# 2020can_master_v6.net
KiCad netlist of a schematic drawn in EAGLE
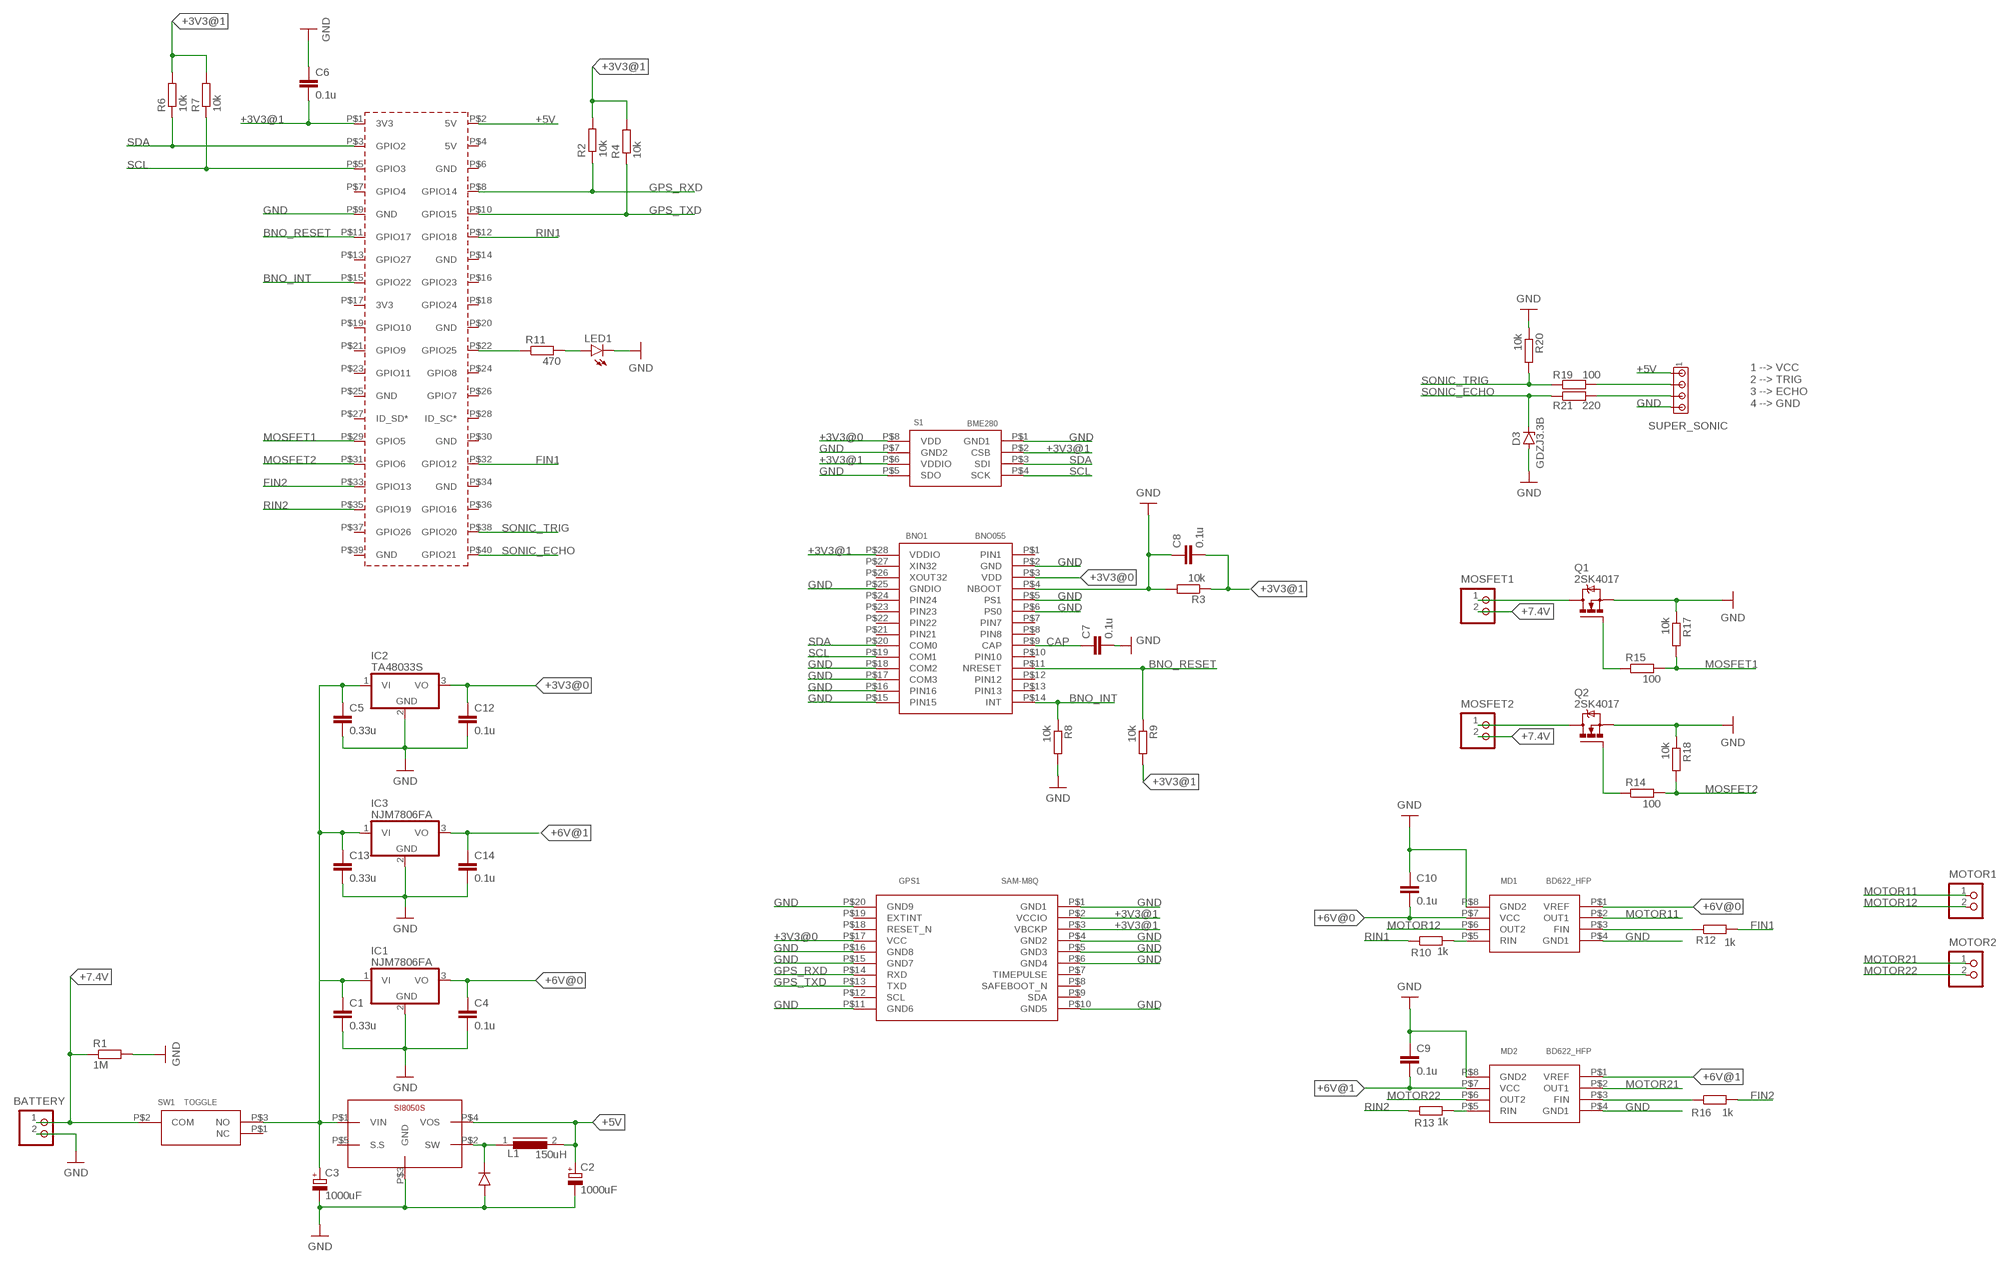
[diagram p0: schematic, sheet 1]

(export (version "E")
  (design (tool "Eeschema 10.0.6"))
  (components
    (comp (ref "BATTERY")
      (value "B2P-VH")
      (footprint "eagle-import:B2P-VH")
      (libsource (lib "eagle-import") (part "B2P-VH"))
    )
    (comp (ref "BNO1")
      (value "BNO055")
      (footprint "eagle-import:BNO055")
      (libsource (lib "eagle-import") (part "BNO055"))
    )
    (comp (ref "C1")
      (value "0.33u")
      (footprint "eagle-import:C5B3")
      (libsource (lib "eagle-import") (part "C5/3"))
    )
    (comp (ref "C2")
      (value "1000uF")
      (footprint "eagle-import:E5-10,5")
      (libsource (lib "eagle-import") (part "CPOL-EUE5-10.5"))
    )
    (comp (ref "C3")
      (value "1000uF")
      (footprint "eagle-import:E5-10,5")
      (libsource (lib "eagle-import") (part "CPOL-EUE5-10.5"))
    )
    (comp (ref "C4")
      (value "0.1u")
      (footprint "eagle-import:C5B3")
      (libsource (lib "eagle-import") (part "C5/3"))
    )
    (comp (ref "C5")
      (value "0.33u")
      (footprint "eagle-import:C5B3")
      (libsource (lib "eagle-import") (part "C5/3"))
    )
    (comp (ref "C6")
      (value "0.1u")
      (footprint "eagle-import:C1608")
      (libsource (lib "eagle-import") (part "C-EUC1608"))
    )
    (comp (ref "C7")
      (value "0.1u")
      (footprint "eagle-import:C1608")
      (libsource (lib "eagle-import") (part "C-EUC1608"))
    )
    (comp (ref "C8")
      (value "0.1u")
      (footprint "eagle-import:C1608")
      (libsource (lib "eagle-import") (part "C-EUC1608"))
    )
    (comp (ref "C9")
      (value "0.1u")
      (footprint "eagle-import:C1608")
      (libsource (lib "eagle-import") (part "C-EUC1608"))
    )
    (comp (ref "C10")
      (value "0.1u")
      (footprint "eagle-import:C1608")
      (libsource (lib "eagle-import") (part "C-EUC1608"))
    )
    (comp (ref "C12")
      (value "0.1u")
      (footprint "eagle-import:C5B3")
      (libsource (lib "eagle-import") (part "C5/3"))
    )
    (comp (ref "C13")
      (value "0.33u")
      (footprint "eagle-import:C5B3")
      (libsource (lib "eagle-import") (part "C5/3"))
    )
    (comp (ref "C14")
      (value "0.1u")
      (footprint "eagle-import:C5B3")
      (libsource (lib "eagle-import") (part "C5/3"))
    )
    (comp (ref "D3")
      (value "GDZJ3.3B")
      (footprint "eagle-import:DO35Z10")
      (libsource (lib "eagle-import") (part "1N821"))
    )
    (comp (ref "DIODE_1.1")
      (value "DIODE_1.5")
      (footprint "eagle-import:DIODE_1.5")
      (libsource (lib "eagle-import") (part "DIODE_1.5"))
    )
    (comp (ref "GPS1")
      (value "SAM-M8Q")
      (footprint "eagle-import:SAM-M8Q")
      (libsource (lib "eagle-import") (part "SAM-M8Q"))
    )
    (comp (ref "IC1")
      (value "NJM7806FA")
      (footprint "eagle-import:TO220V")
      (libsource (lib "eagle-import") (part "78TV6"))
    )
    (comp (ref "IC2")
      (value "TA48033S")
      (footprint "eagle-import:TO220V")
      (libsource (lib "eagle-import") (part "78TV6"))
    )
    (comp (ref "IC3")
      (value "NJM7806FA")
      (footprint "eagle-import:TO220V")
      (libsource (lib "eagle-import") (part "78TV6"))
    )
    (comp (ref "L1")
      (value "150uH")
      (footprint "eagle-import:SFT830D")
      (libsource (lib "eagle-import") (part "SFT830D"))
    )
    (comp (ref "LED1")
      (value "LED5MM")
      (footprint "eagle-import:LED5MM")
      (libsource (lib "eagle-import") (part "LED5MM"))
    )
    (comp (ref "MD1")
      (value "BD622_HFP")
      (footprint "eagle-import:BD62___HRP7")
      (libsource (lib "eagle-import") (part "BD622_HFP"))
    )
    (comp (ref "MD2")
      (value "BD622_HFP")
      (footprint "eagle-import:BD62___HRP7")
      (libsource (lib "eagle-import") (part "BD622_HFP"))
    )
    (comp (ref "MOSFET1")
      (value "B2P-VH")
      (footprint "eagle-import:B2P-VH")
      (libsource (lib "eagle-import") (part "B2P-VH"))
    )
    (comp (ref "MOSFET2")
      (value "B2P-VH")
      (footprint "eagle-import:B2P-VH")
      (libsource (lib "eagle-import") (part "B2P-VH"))
    )
    (comp (ref "MOTOR1")
      (value "B2P-VH")
      (footprint "eagle-import:B2P-VH")
      (libsource (lib "eagle-import") (part "B2P-VH"))
    )
    (comp (ref "MOTOR2")
      (value "B2P-VH")
      (footprint "eagle-import:B2P-VH")
      (libsource (lib "eagle-import") (part "B2P-VH"))
    )
    (comp (ref "PCB1")
      (value "RPI3RPI3")
      (footprint "eagle-import:RPI3")
      (libsource (lib "eagle-import") (part "RPI3RPI3"))
    )
    (comp (ref "Q1")
      (value "2SK4017")
      (footprint "eagle-import:TO220BV")
      (libsource (lib "eagle-import") (part "IRF520"))
    )
    (comp (ref "Q2")
      (value "2SK4017")
      (footprint "eagle-import:TO220BV")
      (libsource (lib "eagle-import") (part "IRF520"))
    )
    (comp (ref "R1")
      (value "1M")
      (footprint "eagle-import:R2012")
      (libsource (lib "eagle-import") (part "R-EU_R2012"))
    )
    (comp (ref "R2")
      (value "10k")
      (footprint "eagle-import:R2012")
      (libsource (lib "eagle-import") (part "R-EU_R2012"))
    )
    (comp (ref "R3")
      (value "10k")
      (footprint "eagle-import:R2012")
      (libsource (lib "eagle-import") (part "R-EU_R2012"))
    )
    (comp (ref "R4")
      (value "10k")
      (footprint "eagle-import:R2012")
      (libsource (lib "eagle-import") (part "R-EU_R2012"))
    )
    (comp (ref "R6")
      (value "10k")
      (footprint "eagle-import:R2012")
      (libsource (lib "eagle-import") (part "R-EU_R2012"))
    )
    (comp (ref "R7")
      (value "10k")
      (footprint "eagle-import:R2012")
      (libsource (lib "eagle-import") (part "R-EU_R2012"))
    )
    (comp (ref "R8")
      (value "10k")
      (footprint "eagle-import:R2012")
      (libsource (lib "eagle-import") (part "R-EU_R2012"))
    )
    (comp (ref "R9")
      (value "10k")
      (footprint "eagle-import:R2012")
      (libsource (lib "eagle-import") (part "R-EU_R2012"))
    )
    (comp (ref "R10")
      (value "1k")
      (footprint "eagle-import:R2012")
      (libsource (lib "eagle-import") (part "R-EU_R2012"))
    )
    (comp (ref "R11")
      (value "470")
      (footprint "eagle-import:0207_10")
      (libsource (lib "eagle-import") (part "R-EU_0207/10"))
    )
    (comp (ref "R12")
      (value "1k")
      (footprint "eagle-import:R2012")
      (libsource (lib "eagle-import") (part "R-EU_R2012"))
    )
    (comp (ref "R13")
      (value "1k")
      (footprint "eagle-import:R2012")
      (libsource (lib "eagle-import") (part "R-EU_R2012"))
    )
    (comp (ref "R14")
      (value "100")
      (footprint "eagle-import:0207_10")
      (libsource (lib "eagle-import") (part "R-EU_0207/10"))
    )
    (comp (ref "R15")
      (value "100")
      (footprint "eagle-import:0207_10")
      (libsource (lib "eagle-import") (part "R-EU_0207/10"))
    )
    (comp (ref "R16")
      (value "1k")
      (footprint "eagle-import:R2012")
      (libsource (lib "eagle-import") (part "R-EU_R2012"))
    )
    (comp (ref "R17")
      (value "10k")
      (footprint "eagle-import:R2012")
      (libsource (lib "eagle-import") (part "R-EU_R2012"))
    )
    (comp (ref "R18")
      (value "10k")
      (footprint "eagle-import:R2012")
      (libsource (lib "eagle-import") (part "R-EU_R2012"))
    )
    (comp (ref "R19")
      (value "100")
      (footprint "eagle-import:0207_10")
      (libsource (lib "eagle-import") (part "R-EU_0207/10"))
    )
    (comp (ref "R20")
      (value "10k")
      (footprint "eagle-import:R2012")
      (libsource (lib "eagle-import") (part "R-EU_R2012"))
    )
    (comp (ref "R21")
      (value "220")
      (footprint "eagle-import:0207_10")
      (libsource (lib "eagle-import") (part "R-EU_0207/10"))
    )
    (comp (ref "S1")
      (value "BME280")
      (footprint "eagle-import:BME280")
      (libsource (lib "eagle-import") (part "BME280"))
    )
    (comp (ref "SI8050S1")
      (value "SI8050S")
      (footprint "eagle-import:SI8050S")
      (libsource (lib "eagle-import") (part "SI8050S"))
    )
    (comp (ref "SUPER_SONIC")
      (value "MTA04-100")
      (footprint "eagle-import:10X04MTA")
      (libsource (lib "eagle-import") (part "MTA04-100"))
    )
    (comp (ref "SW1")
      (value "TOGGLE")
      (footprint "eagle-import:TOGGLE_1MS1-T1-B1-M2-Q-N-S")
      (libsource (lib "eagle-import") (part "TOGGLE_1MS1-T1-B1-M2-Q-N-S"))
    )
  )
  (nets
    (net (code "1") (name "+3V3@0") (class "Default")
      (node (ref "BNO1") (pin "P$3") (pinfunction "VDD_P$3") (pintype "bidirectional"))
      (node (ref "C12") (pin "1") (pinfunction "1_1") (pintype "passive"))
      (node (ref "GPS1") (pin "P$17") (pinfunction "VCC_P$17") (pintype "bidirectional"))
      (node (ref "IC2") (pin "3") (pinfunction "VO_3") (pintype "passive"))
      (node (ref "S1") (pin "P$8") (pinfunction "VDD_P$8") (pintype "bidirectional"))
    )
    (net (code "2") (name "+3V3@1") (class "Default")
      (node (ref "BNO1") (pin "P$28") (pinfunction "VDDIO_P$28") (pintype "bidirectional"))
      (node (ref "C6") (pin "2") (pinfunction "2_2") (pintype "passive"))
      (node (ref "C8") (pin "2") (pinfunction "2_2") (pintype "passive"))
      (node (ref "GPS1") (pin "P$2") (pinfunction "VCCIO_P$2") (pintype "bidirectional"))
      (node (ref "GPS1") (pin "P$3") (pinfunction "VBCKP_P$3") (pintype "bidirectional"))
      (node (ref "PCB1") (pin "P$1") (pinfunction "3V3_P$1") (pintype "bidirectional"))
      (node (ref "R2") (pin "2") (pinfunction "2_2") (pintype "passive"))
      (node (ref "R3") (pin "1") (pinfunction "1_1") (pintype "passive"))
      (node (ref "R4") (pin "2") (pinfunction "2_2") (pintype "passive"))
      (node (ref "R6") (pin "2") (pinfunction "2_2") (pintype "passive"))
      (node (ref "R7") (pin "2") (pinfunction "2_2") (pintype "passive"))
      (node (ref "R9") (pin "2") (pinfunction "2_2") (pintype "passive"))
      (node (ref "S1") (pin "P$2") (pinfunction "CSB_P$2") (pintype "bidirectional"))
      (node (ref "S1") (pin "P$6") (pinfunction "VDDIO_P$6") (pintype "bidirectional"))
    )
    (net (code "3") (name "+5V") (class "Default")
      (node (ref "C2") (pin "+") (pinfunction "+_+") (pintype "passive"))
      (node (ref "L1") (pin "2") (pinfunction "2_2") (pintype "passive"))
      (node (ref "PCB1") (pin "P$2") (pinfunction "5V_P$2") (pintype "bidirectional"))
      (node (ref "SI8050S1") (pin "P$4") (pinfunction "VOS_P$4") (pintype "bidirectional"))
      (node (ref "SUPER_SONIC") (pin "1") (pinfunction "1_1") (pintype "passive"))
    )
    (net (code "4") (name "+6V@0") (class "Default")
      (node (ref "C10") (pin "2") (pinfunction "2_2") (pintype "passive"))
      (node (ref "C4") (pin "1") (pinfunction "1_1") (pintype "passive"))
      (node (ref "IC1") (pin "3") (pinfunction "VO_3") (pintype "passive"))
      (node (ref "MD1") (pin "P$1") (pinfunction "VREF_P$1") (pintype "bidirectional"))
      (node (ref "MD1") (pin "P$7") (pinfunction "VCC_P$7") (pintype "bidirectional"))
    )
    (net (code "5") (name "+6V@1") (class "Default")
      (node (ref "C14") (pin "1") (pinfunction "1_1") (pintype "passive"))
      (node (ref "C9") (pin "2") (pinfunction "2_2") (pintype "passive"))
      (node (ref "IC3") (pin "3") (pinfunction "VO_3") (pintype "passive"))
      (node (ref "MD2") (pin "P$1") (pinfunction "VREF_P$1") (pintype "bidirectional"))
      (node (ref "MD2") (pin "P$7") (pinfunction "VCC_P$7") (pintype "bidirectional"))
    )
    (net (code "6") (name "+7.4V") (class "Default")
      (node (ref "BATTERY") (pin "1") (pinfunction "1_1") (pintype "passive"))
      (node (ref "MOSFET1") (pin "2") (pinfunction "2_2") (pintype "passive"))
      (node (ref "MOSFET2") (pin "2") (pinfunction "2_2") (pintype "passive"))
      (node (ref "R1") (pin "1") (pinfunction "1_1") (pintype "passive"))
      (node (ref "SW1") (pin "P$2") (pinfunction "COM_P$2") (pintype "bidirectional"))
    )
    (net (code "7") (name "/BNO_INT") (class "Default")
      (node (ref "BNO1") (pin "P$14") (pinfunction "INT_P$14") (pintype "bidirectional"))
      (node (ref "PCB1") (pin "P$15") (pinfunction "GPIO22_P$15") (pintype "bidirectional"))
      (node (ref "R8") (pin "1") (pinfunction "1_1") (pintype "passive"))
    )
    (net (code "8") (name "/BNO_RESET") (class "Default")
      (node (ref "BNO1") (pin "P$11") (pinfunction "NRESET_P$11") (pintype "bidirectional"))
      (node (ref "PCB1") (pin "P$11") (pinfunction "GPIO17_P$11") (pintype "bidirectional"))
      (node (ref "R9") (pin "1") (pinfunction "1_1") (pintype "passive"))
    )
    (net (code "9") (name "/CAP") (class "Default")
      (node (ref "BNO1") (pin "P$9") (pinfunction "CAP_P$9") (pintype "bidirectional"))
      (node (ref "C7") (pin "1") (pinfunction "1_1") (pintype "passive"))
    )
    (net (code "10") (name "/FIN1") (class "Default")
      (node (ref "PCB1") (pin "P$32") (pinfunction "GPIO12_P$32") (pintype "bidirectional"))
      (node (ref "R12") (pin "2") (pinfunction "2_2") (pintype "passive"))
    )
    (net (code "11") (name "/FIN2") (class "Default")
      (node (ref "PCB1") (pin "P$33") (pinfunction "GPIO13_P$33") (pintype "bidirectional"))
      (node (ref "R16") (pin "2") (pinfunction "2_2") (pintype "passive"))
    )
    (net (code "12") (name "/GPS_RXD") (class "Default")
      (node (ref "GPS1") (pin "P$14") (pinfunction "RXD_P$14") (pintype "bidirectional"))
      (node (ref "PCB1") (pin "P$8") (pinfunction "GPIO14_P$8") (pintype "bidirectional"))
      (node (ref "R2") (pin "1") (pinfunction "1_1") (pintype "passive"))
    )
    (net (code "13") (name "/GPS_TXD") (class "Default")
      (node (ref "GPS1") (pin "P$13") (pinfunction "TXD_P$13") (pintype "bidirectional"))
      (node (ref "PCB1") (pin "P$10") (pinfunction "GPIO15_P$10") (pintype "bidirectional"))
      (node (ref "R4") (pin "1") (pinfunction "1_1") (pintype "passive"))
    )
    (net (code "14") (name "/MOSFET1") (class "Default")
      (node (ref "PCB1") (pin "P$29") (pinfunction "GPIO5_P$29") (pintype "bidirectional"))
      (node (ref "R15") (pin "2") (pinfunction "2_2") (pintype "passive"))
      (node (ref "R17") (pin "2") (pinfunction "2_2") (pintype "passive"))
    )
    (net (code "15") (name "/MOSFET2") (class "Default")
      (node (ref "PCB1") (pin "P$31") (pinfunction "GPIO6_P$31") (pintype "bidirectional"))
      (node (ref "R14") (pin "2") (pinfunction "2_2") (pintype "passive"))
      (node (ref "R18") (pin "2") (pinfunction "2_2") (pintype "passive"))
    )
    (net (code "16") (name "/MOTOR11") (class "Default")
      (node (ref "MD1") (pin "P$2") (pinfunction "OUT1_P$2") (pintype "bidirectional"))
      (node (ref "MOTOR1") (pin "1") (pinfunction "1_1") (pintype "passive"))
    )
    (net (code "17") (name "/MOTOR12") (class "Default")
      (node (ref "MD1") (pin "P$6") (pinfunction "OUT2_P$6") (pintype "bidirectional"))
      (node (ref "MOTOR1") (pin "2") (pinfunction "2_2") (pintype "passive"))
    )
    (net (code "18") (name "/MOTOR21") (class "Default")
      (node (ref "MD2") (pin "P$2") (pinfunction "OUT1_P$2") (pintype "bidirectional"))
      (node (ref "MOTOR2") (pin "1") (pinfunction "1_1") (pintype "passive"))
    )
    (net (code "19") (name "/MOTOR22") (class "Default")
      (node (ref "MD2") (pin "P$6") (pinfunction "OUT2_P$6") (pintype "bidirectional"))
      (node (ref "MOTOR2") (pin "2") (pinfunction "2_2") (pintype "passive"))
    )
    (net (code "20") (name "/RIN1") (class "Default")
      (node (ref "PCB1") (pin "P$12") (pinfunction "GPIO18_P$12") (pintype "bidirectional"))
      (node (ref "R10") (pin "1") (pinfunction "1_1") (pintype "passive"))
    )
    (net (code "21") (name "/RIN2") (class "Default")
      (node (ref "PCB1") (pin "P$35") (pinfunction "GPIO19_P$35") (pintype "bidirectional"))
      (node (ref "R13") (pin "1") (pinfunction "1_1") (pintype "passive"))
    )
    (net (code "22") (name "/SCL") (class "Default")
      (node (ref "BNO1") (pin "P$19") (pinfunction "COM1_P$19") (pintype "bidirectional"))
      (node (ref "PCB1") (pin "P$5") (pinfunction "GPIO3_P$5") (pintype "bidirectional"))
      (node (ref "R7") (pin "1") (pinfunction "1_1") (pintype "passive"))
      (node (ref "S1") (pin "P$4") (pinfunction "SCK_P$4") (pintype "bidirectional"))
    )
    (net (code "23") (name "/SDA") (class "Default")
      (node (ref "BNO1") (pin "P$20") (pinfunction "COM0_P$20") (pintype "bidirectional"))
      (node (ref "PCB1") (pin "P$3") (pinfunction "GPIO2_P$3") (pintype "bidirectional"))
      (node (ref "R6") (pin "1") (pinfunction "1_1") (pintype "passive"))
      (node (ref "S1") (pin "P$3") (pinfunction "SDI_P$3") (pintype "bidirectional"))
    )
    (net (code "24") (name "/SONIC_ECHO") (class "Default")
      (node (ref "D3") (pin "C") (pinfunction "C_C") (pintype "passive"))
      (node (ref "PCB1") (pin "P$40") (pinfunction "GPIO21_P$40") (pintype "bidirectional"))
      (node (ref "R21") (pin "1") (pinfunction "1_1") (pintype "passive"))
    )
    (net (code "25") (name "/SONIC_TRIG") (class "Default")
      (node (ref "PCB1") (pin "P$38") (pinfunction "GPIO20_P$38") (pintype "bidirectional"))
      (node (ref "R19") (pin "1") (pinfunction "1_1") (pintype "passive"))
      (node (ref "R20") (pin "2") (pinfunction "2_2") (pintype "passive"))
    )
    (net (code "26") (name "GND") (class "Default")
      (node (ref "BATTERY") (pin "2") (pinfunction "2_2") (pintype "passive"))
      (node (ref "BNO1") (pin "P$15") (pinfunction "PIN15_P$15") (pintype "bidirectional"))
      (node (ref "BNO1") (pin "P$16") (pinfunction "PIN16_P$16") (pintype "bidirectional"))
      (node (ref "BNO1") (pin "P$17") (pinfunction "COM3_P$17") (pintype "bidirectional"))
      (node (ref "BNO1") (pin "P$18") (pinfunction "COM2_P$18") (pintype "bidirectional"))
      (node (ref "BNO1") (pin "P$2") (pinfunction "GND_P$2") (pintype "bidirectional"))
      (node (ref "BNO1") (pin "P$25") (pinfunction "GNDIO_P$25") (pintype "bidirectional"))
      (node (ref "BNO1") (pin "P$4") (pinfunction "NBOOT_P$4") (pintype "bidirectional"))
      (node (ref "BNO1") (pin "P$5") (pinfunction "PS1_P$5") (pintype "bidirectional"))
      (node (ref "BNO1") (pin "P$6") (pinfunction "PS0_P$6") (pintype "bidirectional"))
      (node (ref "C1") (pin "2") (pinfunction "2_2") (pintype "passive"))
      (node (ref "C10") (pin "1") (pinfunction "1_1") (pintype "passive"))
      (node (ref "C12") (pin "2") (pinfunction "2_2") (pintype "passive"))
      (node (ref "C2") (pin "-") (pinfunction "-_-") (pintype "passive"))
      (node (ref "C3") (pin "-") (pinfunction "-_-") (pintype "passive"))
      (node (ref "C4") (pin "2") (pinfunction "2_2") (pintype "passive"))
      (node (ref "C5") (pin "2") (pinfunction "2_2") (pintype "passive"))
      (node (ref "C6") (pin "1") (pinfunction "1_1") (pintype "passive"))
      (node (ref "C7") (pin "2") (pinfunction "2_2") (pintype "passive"))
      (node (ref "C8") (pin "1") (pinfunction "1_1") (pintype "passive"))
      (node (ref "C9") (pin "1") (pinfunction "1_1") (pintype "passive"))
      (node (ref "D3") (pin "A") (pinfunction "A_A") (pintype "passive"))
      (node (ref "DIODE_1.1") (pin "P$1") (pinfunction "ANODE_P$1") (pintype "bidirectional"))
      (node (ref "GPS1") (pin "P$1") (pinfunction "GND1_P$1") (pintype "bidirectional"))
      (node (ref "GPS1") (pin "P$10") (pinfunction "GND5_P$10") (pintype "bidirectional"))
      (node (ref "GPS1") (pin "P$11") (pinfunction "GND6_P$11") (pintype "bidirectional"))
      (node (ref "GPS1") (pin "P$15") (pinfunction "GND7_P$15") (pintype "bidirectional"))
      (node (ref "GPS1") (pin "P$16") (pinfunction "GND8_P$16") (pintype "bidirectional"))
      (node (ref "GPS1") (pin "P$20") (pinfunction "GND9_P$20") (pintype "bidirectional"))
      (node (ref "GPS1") (pin "P$4") (pinfunction "GND2_P$4") (pintype "bidirectional"))
      (node (ref "GPS1") (pin "P$5") (pinfunction "GND3_P$5") (pintype "bidirectional"))
      (node (ref "GPS1") (pin "P$6") (pinfunction "GND4_P$6") (pintype "bidirectional"))
      (node (ref "IC1") (pin "2") (pinfunction "GND_2") (pintype "passive"))
      (node (ref "IC2") (pin "2") (pinfunction "GND_2") (pintype "passive"))
      (node (ref "LED1") (pin "K") (pinfunction "C_K") (pintype "passive"))
      (node (ref "MD1") (pin "P$4") (pinfunction "GND1_P$4") (pintype "bidirectional"))
      (node (ref "MD1") (pin "P$8") (pinfunction "GND2_P$8") (pintype "bidirectional"))
      (node (ref "MD2") (pin "P$4") (pinfunction "GND1_P$4") (pintype "bidirectional"))
      (node (ref "MD2") (pin "P$8") (pinfunction "GND2_P$8") (pintype "bidirectional"))
      (node (ref "PCB1") (pin "P$9") (pinfunction "GND_P$9") (pintype "bidirectional"))
      (node (ref "Q1") (pin "S") (pinfunction "S_S") (pintype "passive"))
      (node (ref "Q2") (pin "S") (pinfunction "S_S") (pintype "passive"))
      (node (ref "R1") (pin "2") (pinfunction "2_2") (pintype "passive"))
      (node (ref "R17") (pin "1") (pinfunction "1_1") (pintype "passive"))
      (node (ref "R18") (pin "1") (pinfunction "1_1") (pintype "passive"))
      (node (ref "R20") (pin "1") (pinfunction "1_1") (pintype "passive"))
      (node (ref "R3") (pin "2") (pinfunction "2_2") (pintype "passive"))
      (node (ref "R8") (pin "2") (pinfunction "2_2") (pintype "passive"))
      (node (ref "S1") (pin "P$1") (pinfunction "GND1_P$1") (pintype "bidirectional"))
      (node (ref "S1") (pin "P$5") (pinfunction "SDO_P$5") (pintype "bidirectional"))
      (node (ref "S1") (pin "P$7") (pinfunction "GND2_P$7") (pintype "bidirectional"))
      (node (ref "SI8050S1") (pin "P$3") (pinfunction "GND_P$3") (pintype "bidirectional"))
      (node (ref "SUPER_SONIC") (pin "4") (pinfunction "4_4") (pintype "passive"))
    )
    (net (code "27") (name "Net-(DIODE_1.1-CATHODE)") (class "Default")
      (node (ref "DIODE_1.1") (pin "P$2") (pinfunction "CATHODE_P$2") (pintype "bidirectional"))
      (node (ref "L1") (pin "1") (pinfunction "1_1") (pintype "passive"))
      (node (ref "SI8050S1") (pin "P$2") (pinfunction "SW_P$2") (pintype "bidirectional"))
    )
    (net (code "28") (name "Net-(IC1-VI)") (class "Default")
      (node (ref "C1") (pin "1") (pinfunction "1_1") (pintype "passive"))
      (node (ref "C13") (pin "1") (pinfunction "1_1") (pintype "passive"))
      (node (ref "C3") (pin "+") (pinfunction "+_+") (pintype "passive"))
      (node (ref "C5") (pin "1") (pinfunction "1_1") (pintype "passive"))
      (node (ref "IC1") (pin "1") (pinfunction "VI_1") (pintype "input"))
      (node (ref "IC2") (pin "1") (pinfunction "VI_1") (pintype "input"))
      (node (ref "IC3") (pin "1") (pinfunction "VI_1") (pintype "input"))
      (node (ref "SI8050S1") (pin "P$1") (pinfunction "VIN_P$1") (pintype "bidirectional"))
      (node (ref "SW1") (pin "P$3") (pinfunction "NO_P$3") (pintype "bidirectional"))
    )
    (net (code "29") (name "Net-(IC3-GND)") (class "Default")
      (node (ref "C13") (pin "2") (pinfunction "2_2") (pintype "passive"))
      (node (ref "C14") (pin "2") (pinfunction "2_2") (pintype "passive"))
      (node (ref "IC3") (pin "2") (pinfunction "GND_2") (pintype "passive"))
    )
    (net (code "30") (name "Net-(LED1-PadA)") (class "Default")
      (node (ref "LED1") (pin "A") (pinfunction "A_A") (pintype "passive"))
      (node (ref "R11") (pin "2") (pinfunction "2_2") (pintype "passive"))
    )
    (net (code "31") (name "Net-(MD1-FIN)") (class "Default")
      (node (ref "MD1") (pin "P$3") (pinfunction "FIN_P$3") (pintype "bidirectional"))
      (node (ref "R12") (pin "1") (pinfunction "1_1") (pintype "passive"))
    )
    (net (code "32") (name "Net-(MD1-RIN)") (class "Default")
      (node (ref "MD1") (pin "P$5") (pinfunction "RIN_P$5") (pintype "bidirectional"))
      (node (ref "R10") (pin "2") (pinfunction "2_2") (pintype "passive"))
    )
    (net (code "33") (name "Net-(MD2-FIN)") (class "Default")
      (node (ref "MD2") (pin "P$3") (pinfunction "FIN_P$3") (pintype "bidirectional"))
      (node (ref "R16") (pin "1") (pinfunction "1_1") (pintype "passive"))
    )
    (net (code "34") (name "Net-(MD2-RIN)") (class "Default")
      (node (ref "MD2") (pin "P$5") (pinfunction "RIN_P$5") (pintype "bidirectional"))
      (node (ref "R13") (pin "2") (pinfunction "2_2") (pintype "passive"))
    )
    (net (code "35") (name "Net-(MOSFET1-Pad1)") (class "Default")
      (node (ref "MOSFET1") (pin "1") (pinfunction "1_1") (pintype "passive"))
      (node (ref "Q1") (pin "D") (pinfunction "D_D") (pintype "passive"))
    )
    (net (code "36") (name "Net-(MOSFET2-Pad1)") (class "Default")
      (node (ref "MOSFET2") (pin "1") (pinfunction "1_1") (pintype "passive"))
      (node (ref "Q2") (pin "D") (pinfunction "D_D") (pintype "passive"))
    )
    (net (code "37") (name "Net-(PCB1-GPIO25)") (class "Default")
      (node (ref "PCB1") (pin "P$22") (pinfunction "GPIO25_P$22") (pintype "bidirectional"))
      (node (ref "R11") (pin "1") (pinfunction "1_1") (pintype "passive"))
    )
    (net (code "38") (name "Net-(Q1-PadG)") (class "Default")
      (node (ref "Q1") (pin "G") (pinfunction "G_G") (pintype "passive"))
      (node (ref "R15") (pin "1") (pinfunction "1_1") (pintype "passive"))
    )
    (net (code "39") (name "Net-(Q2-PadG)") (class "Default")
      (node (ref "Q2") (pin "G") (pinfunction "G_G") (pintype "passive"))
      (node (ref "R14") (pin "1") (pinfunction "1_1") (pintype "passive"))
    )
    (net (code "40") (name "Net-(R19-Pad2)") (class "Default")
      (node (ref "R19") (pin "2") (pinfunction "2_2") (pintype "passive"))
      (node (ref "SUPER_SONIC") (pin "2") (pinfunction "2_2") (pintype "passive"))
    )
    (net (code "41") (name "Net-(R21-Pad2)") (class "Default")
      (node (ref "R21") (pin "2") (pinfunction "2_2") (pintype "passive"))
      (node (ref "SUPER_SONIC") (pin "3") (pinfunction "3_3") (pintype "passive"))
    )
    (net (code "42") (name "unconnected-(BNO1-PIN1-PadP$1)") (class "Default")
      (node (ref "BNO1") (pin "P$1") (pinfunction "PIN1_P$1") (pintype "bidirectional"))
    )
    (net (code "43") (name "unconnected-(BNO1-PIN7-PadP$7)") (class "Default")
      (node (ref "BNO1") (pin "P$7") (pinfunction "PIN7_P$7") (pintype "bidirectional"))
    )
    (net (code "44") (name "unconnected-(BNO1-PIN8-PadP$8)") (class "Default")
      (node (ref "BNO1") (pin "P$8") (pinfunction "PIN8_P$8") (pintype "bidirectional"))
    )
    (net (code "45") (name "unconnected-(BNO1-PIN10-PadP$10)") (class "Default")
      (node (ref "BNO1") (pin "P$10") (pinfunction "PIN10_P$10") (pintype "bidirectional"))
    )
    (net (code "46") (name "unconnected-(BNO1-PIN12-PadP$12)") (class "Default")
      (node (ref "BNO1") (pin "P$12") (pinfunction "PIN12_P$12") (pintype "bidirectional"))
    )
    (net (code "47") (name "unconnected-(BNO1-PIN13-PadP$13)") (class "Default")
      (node (ref "BNO1") (pin "P$13") (pinfunction "PIN13_P$13") (pintype "bidirectional"))
    )
    (net (code "48") (name "unconnected-(BNO1-PIN21-PadP$21)") (class "Default")
      (node (ref "BNO1") (pin "P$21") (pinfunction "PIN21_P$21") (pintype "bidirectional"))
    )
    (net (code "49") (name "unconnected-(BNO1-PIN22-PadP$22)") (class "Default")
      (node (ref "BNO1") (pin "P$22") (pinfunction "PIN22_P$22") (pintype "bidirectional"))
    )
    (net (code "50") (name "unconnected-(BNO1-PIN23-PadP$23)") (class "Default")
      (node (ref "BNO1") (pin "P$23") (pinfunction "PIN23_P$23") (pintype "bidirectional"))
    )
    (net (code "51") (name "unconnected-(BNO1-PIN24-PadP$24)") (class "Default")
      (node (ref "BNO1") (pin "P$24") (pinfunction "PIN24_P$24") (pintype "bidirectional"))
    )
    (net (code "52") (name "unconnected-(BNO1-XIN32-PadP$27)") (class "Default")
      (node (ref "BNO1") (pin "P$27") (pinfunction "XIN32_P$27") (pintype "bidirectional"))
    )
    (net (code "53") (name "unconnected-(BNO1-XOUT32-PadP$26)") (class "Default")
      (node (ref "BNO1") (pin "P$26") (pinfunction "XOUT32_P$26") (pintype "bidirectional"))
    )
    (net (code "54") (name "unconnected-(GPS1-EXTINT-PadP$19)") (class "Default")
      (node (ref "GPS1") (pin "P$19") (pinfunction "EXTINT_P$19") (pintype "bidirectional"))
    )
    (net (code "55") (name "unconnected-(GPS1-RESET_N-PadP$18)") (class "Default")
      (node (ref "GPS1") (pin "P$18") (pinfunction "RESET_N_P$18") (pintype "bidirectional"))
    )
    (net (code "56") (name "unconnected-(GPS1-SAFEBOOT_N-PadP$8)") (class "Default")
      (node (ref "GPS1") (pin "P$8") (pinfunction "SAFEBOOT_N_P$8") (pintype "bidirectional"))
    )
    (net (code "57") (name "unconnected-(GPS1-SCL-PadP$12)") (class "Default")
      (node (ref "GPS1") (pin "P$12") (pinfunction "SCL_P$12") (pintype "bidirectional"))
    )
    (net (code "58") (name "unconnected-(GPS1-SDA-PadP$9)") (class "Default")
      (node (ref "GPS1") (pin "P$9") (pinfunction "SDA_P$9") (pintype "bidirectional"))
    )
    (net (code "59") (name "unconnected-(GPS1-TIMEPULSE-PadP$7)") (class "Default")
      (node (ref "GPS1") (pin "P$7") (pinfunction "TIMEPULSE_P$7") (pintype "bidirectional"))
    )
    (net (code "60") (name "unconnected-(PCB1-3V3-PadP$17)") (class "Default")
      (node (ref "PCB1") (pin "P$17") (pinfunction "3V3_P$17") (pintype "bidirectional"))
    )
    (net (code "61") (name "unconnected-(PCB1-5V-PadP$4)") (class "Default")
      (node (ref "PCB1") (pin "P$4") (pinfunction "5V_P$4") (pintype "bidirectional"))
    )
    (net (code "62") (name "unconnected-(PCB1-GND-PadP$6)") (class "Default")
      (node (ref "PCB1") (pin "P$6") (pinfunction "GND_P$6") (pintype "bidirectional"))
    )
    (net (code "63") (name "unconnected-(PCB1-GND-PadP$14)") (class "Default")
      (node (ref "PCB1") (pin "P$14") (pinfunction "GND_P$14") (pintype "bidirectional"))
    )
    (net (code "64") (name "unconnected-(PCB1-GND-PadP$20)") (class "Default")
      (node (ref "PCB1") (pin "P$20") (pinfunction "GND_P$20") (pintype "bidirectional"))
    )
    (net (code "65") (name "unconnected-(PCB1-GND-PadP$25)") (class "Default")
      (node (ref "PCB1") (pin "P$25") (pinfunction "GND_P$25") (pintype "bidirectional"))
    )
    (net (code "66") (name "unconnected-(PCB1-GND-PadP$30)") (class "Default")
      (node (ref "PCB1") (pin "P$30") (pinfunction "GND_P$30") (pintype "bidirectional"))
    )
    (net (code "67") (name "unconnected-(PCB1-GND-PadP$34)") (class "Default")
      (node (ref "PCB1") (pin "P$34") (pinfunction "GND_P$34") (pintype "bidirectional"))
    )
    (net (code "68") (name "unconnected-(PCB1-GND-PadP$39)") (class "Default")
      (node (ref "PCB1") (pin "P$39") (pinfunction "GND_P$39") (pintype "bidirectional"))
    )
    (net (code "69") (name "unconnected-(PCB1-GPIO4-PadP$7)") (class "Default")
      (node (ref "PCB1") (pin "P$7") (pinfunction "GPIO4_P$7") (pintype "bidirectional"))
    )
    (net (code "70") (name "unconnected-(PCB1-GPIO7-PadP$26)") (class "Default")
      (node (ref "PCB1") (pin "P$26") (pinfunction "GPIO7_P$26") (pintype "bidirectional"))
    )
    (net (code "71") (name "unconnected-(PCB1-GPIO8-PadP$24)") (class "Default")
      (node (ref "PCB1") (pin "P$24") (pinfunction "GPIO8_P$24") (pintype "bidirectional"))
    )
    (net (code "72") (name "unconnected-(PCB1-GPIO9-PadP$21)") (class "Default")
      (node (ref "PCB1") (pin "P$21") (pinfunction "GPIO9_P$21") (pintype "bidirectional"))
    )
    (net (code "73") (name "unconnected-(PCB1-GPIO10-PadP$19)") (class "Default")
      (node (ref "PCB1") (pin "P$19") (pinfunction "GPIO10_P$19") (pintype "bidirectional"))
    )
    (net (code "74") (name "unconnected-(PCB1-GPIO11-PadP$23)") (class "Default")
      (node (ref "PCB1") (pin "P$23") (pinfunction "GPIO11_P$23") (pintype "bidirectional"))
    )
    (net (code "75") (name "unconnected-(PCB1-GPIO16-PadP$36)") (class "Default")
      (node (ref "PCB1") (pin "P$36") (pinfunction "GPIO16_P$36") (pintype "bidirectional"))
    )
    (net (code "76") (name "unconnected-(PCB1-GPIO23-PadP$16)") (class "Default")
      (node (ref "PCB1") (pin "P$16") (pinfunction "GPIO23_P$16") (pintype "bidirectional"))
    )
    (net (code "77") (name "unconnected-(PCB1-GPIO24-PadP$18)") (class "Default")
      (node (ref "PCB1") (pin "P$18") (pinfunction "GPIO24_P$18") (pintype "bidirectional"))
    )
    (net (code "78") (name "unconnected-(PCB1-GPIO26-PadP$37)") (class "Default")
      (node (ref "PCB1") (pin "P$37") (pinfunction "GPIO26_P$37") (pintype "bidirectional"))
    )
    (net (code "79") (name "unconnected-(PCB1-GPIO27-PadP$13)") (class "Default")
      (node (ref "PCB1") (pin "P$13") (pinfunction "GPIO27_P$13") (pintype "bidirectional"))
    )
    (net (code "80") (name "unconnected-(PCB1-ID_SC*-PadP$28)") (class "Default")
      (node (ref "PCB1") (pin "P$28") (pinfunction "ID_SC*_P$28") (pintype "bidirectional"))
    )
    (net (code "81") (name "unconnected-(PCB1-ID_SD*-PadP$27)") (class "Default")
      (node (ref "PCB1") (pin "P$27") (pinfunction "ID_SD*_P$27") (pintype "bidirectional"))
    )
    (net (code "82") (name "unconnected-(SI8050S1-S.S-PadP$5)") (class "Default")
      (node (ref "SI8050S1") (pin "P$5") (pinfunction "S.S_P$5") (pintype "bidirectional"))
    )
    (net (code "83") (name "unconnected-(SW1-NC-PadP$1)") (class "Default")
      (node (ref "SW1") (pin "P$1") (pinfunction "NC_P$1") (pintype "bidirectional"))
    )
  )
)
